# DSO_Control.net
KiCad netlist of a schematic drawn in Altium Designer
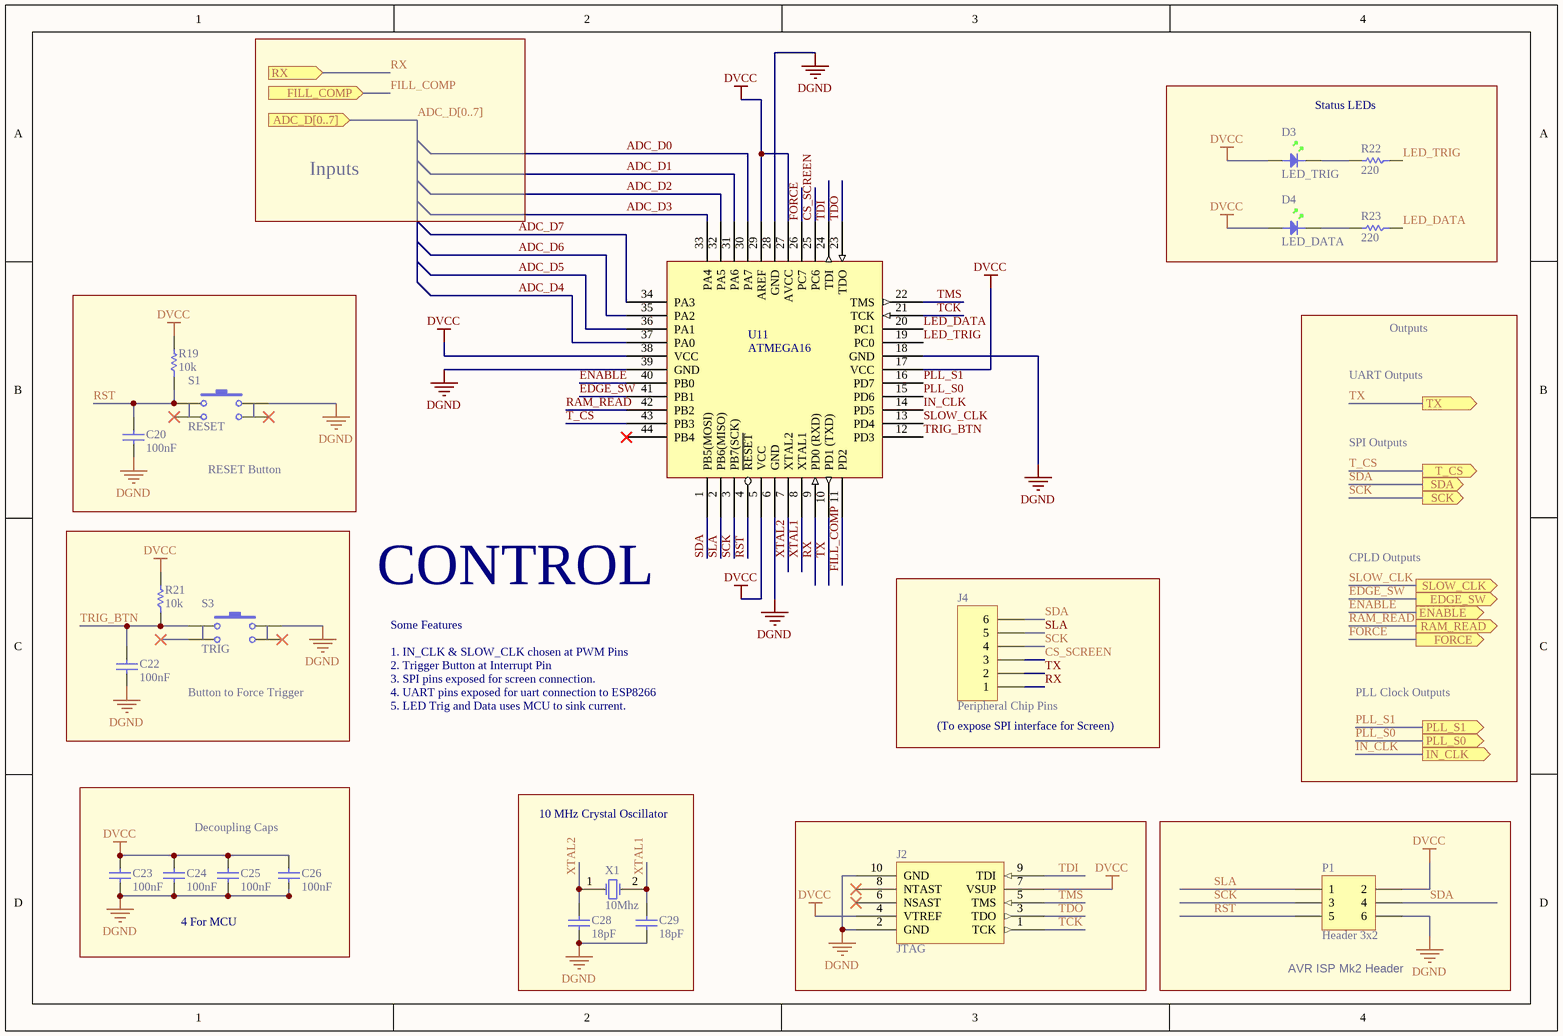
[diagram p0: DSO_Control.SchDoc]

(export (version "E")
  (design (tool "Eeschema 10.0.6"))
  (components
    (comp (ref "C20")
      (value "100nF")
      (footprint "0805C")
      (description "Capacitor")
      (fields (field (name "REVIEWED BY") "RM - 2018/08/05"))
      (libsource (lib "DSO") (part "C"))
    )
    (comp (ref "C22")
      (value "100nF")
      (footprint "0805C")
      (description "Capacitor")
      (fields (field (name "REVIEWED BY") "RM - 2018/08/05"))
      (libsource (lib "DSO") (part "C"))
    )
    (comp (ref "C23")
      (value "100nF")
      (footprint "0805C")
      (description "Capacitor")
      (fields (field (name "REVIEWED BY") "RM - 2018/08/05"))
      (libsource (lib "DSO") (part "C"))
    )
    (comp (ref "C24")
      (value "100nF")
      (footprint "0805C")
      (description "Capacitor")
      (fields (field (name "REVIEWED BY") "RM - 2018/08/05"))
      (libsource (lib "DSO") (part "C"))
    )
    (comp (ref "C25")
      (value "100nF")
      (footprint "0805C")
      (description "Capacitor")
      (fields (field (name "REVIEWED BY") "RM - 2018/08/05"))
      (libsource (lib "DSO") (part "C"))
    )
    (comp (ref "C26")
      (value "100nF")
      (footprint "0805C")
      (description "Capacitor")
      (fields (field (name "REVIEWED BY") "RM - 2018/08/05"))
      (libsource (lib "DSO") (part "C"))
    )
    (comp (ref "C28")
      (value "18pF")
      (footprint "0805C")
      (description "Capacitor")
      (fields (field (name "REVIEWED BY") "RM - 2018/08/05"))
      (libsource (lib "DSO") (part "C"))
    )
    (comp (ref "C29")
      (value "18pF")
      (footprint "0805C")
      (description "Capacitor")
      (fields (field (name "REVIEWED BY") "RM - 2018/08/05"))
      (libsource (lib "DSO") (part "C"))
    )
    (comp (ref "D3")
      (value "LED_TRIG")
      (footprint "0805D-GREEN")
      (description "Light Emitting Diode")
      (fields (field (name "REVIEWED BY") "RM - 2018/08/05"))
      (libsource (lib "DSO") (part "LED GREEN"))
    )
    (comp (ref "D4")
      (value "LED_DATA")
      (footprint "0805D-GREEN")
      (description "Light Emitting Diode")
      (fields (field (name "REVIEWED BY") "RM - 2018/08/05"))
      (libsource (lib "DSO") (part "LED GREEN"))
    )
    (comp (ref "J2")
      (value "JTAG")
      (footprint "BOXEDVERT10")
      (description "JTAG_CON")
      (fields (field (name "REVIEWED BY") "RM - 2018/08/05"))
      (libsource (lib "DSO") (part "JTAG_CON"))
    )
    (comp (ref "J4")
      (value "Peripheral Chip Pins")
      (footprint "HDR1X6")
      (description "Header, 6-Pin")
      (libsource (lib "DSO") (part "Header 6"))
    )
    (comp (ref "P1")
      (value "Header 3x2")
      (footprint "HDR3x2")
      (description "Header, 5-Pin")
      (fields (field (name "REVIEWED BY") "RM - 2018/08/05"))
      (libsource (lib "DSO") (part "Header 3x2"))
    )
    (comp (ref "R19")
      (value "10k")
      (footprint "0805")
      (description "Resistor")
      (fields (field (name "REVIEWED BY") "RM - 2018/08/05"))
      (libsource (lib "DSO") (part "R"))
    )
    (comp (ref "R21")
      (value "10k")
      (footprint "0805")
      (description "Resistor")
      (fields (field (name "REVIEWED BY") "RM - 2018/08/05"))
      (libsource (lib "DSO") (part "R"))
    )
    (comp (ref "R22")
      (value "220")
      (footprint "0805")
      (description "Resistor")
      (fields (field (name "REVIEWED BY") "RM - 2018/08/05"))
      (libsource (lib "DSO") (part "R"))
    )
    (comp (ref "R23")
      (value "220")
      (footprint "0805")
      (description "Resistor")
      (fields (field (name "REVIEWED BY") "RM - 2018/08/05"))
      (libsource (lib "DSO") (part "R"))
    )
    (comp (ref "S1")
      (value "RESET")
      (footprint "SPST PB SWITCH SMD")
      (description "Momentary Push Button Switch 1P 1T 2pins")
      (fields (field (name "REVIEWED BY") "RM - 2018/08/05"))
      (libsource (lib "DSO") (part "SW_PB_1P1T4"))
    )
    (comp (ref "S3")
      (value "TRIG")
      (footprint "SPST PB SWITCH SMD")
      (description "Momentary Push Button Switch 1P 1T 2pins")
      (fields (field (name "REVIEWED BY") "RM - 2018/08/05"))
      (libsource (lib "DSO") (part "SW_PB_1P1T4"))
    )
    (comp (ref "U11")
      (value "ATMEGA16")
      (footprint "QFP-48")
      (description "ATMEGA16 Microcontroller")
      (fields (field (name "REVIEWED BY") "RM - 2018/08/05"))
      (libsource (lib "DSO") (part "ATMEGA16"))
    )
    (comp (ref "X1")
      (value "10Mhz")
      (footprint "XTAL_FLAT_SMD")
      (description "Crystal Oscillator")
      (fields (field (name "REVIEWED BY") "RM - 2018/08/05"))
      (libsource (lib "DSO") (part "XTAL"))
    )
  )
  (nets
    (net (code "1") (name "/ADC_D0") (class "Default")
      (node (ref "U11") (pin "30") (pinfunction "PA7_30") (pintype "passive"))
    )
    (net (code "2") (name "/ADC_D1") (class "Default")
      (node (ref "U11") (pin "31") (pinfunction "PA6_31") (pintype "passive"))
    )
    (net (code "3") (name "/ADC_D2") (class "Default")
      (node (ref "U11") (pin "32") (pinfunction "PA5_32") (pintype "passive"))
    )
    (net (code "4") (name "/ADC_D3") (class "Default")
      (node (ref "U11") (pin "33") (pinfunction "PA4_33") (pintype "passive"))
    )
    (net (code "5") (name "/ADC_D4") (class "Default")
      (node (ref "U11") (pin "37") (pinfunction "PA0_37") (pintype "passive"))
    )
    (net (code "6") (name "/ADC_D5") (class "Default")
      (node (ref "U11") (pin "36") (pinfunction "PA1_36") (pintype "passive"))
    )
    (net (code "7") (name "/ADC_D6") (class "Default")
      (node (ref "U11") (pin "35") (pinfunction "PA2_35") (pintype "passive"))
    )
    (net (code "8") (name "/ADC_D7") (class "Default")
      (node (ref "U11") (pin "34") (pinfunction "PA3_34") (pintype "passive"))
    )
    (net (code "10") (name "/CS_SCREEN") (class "Default")
      (node (ref "J4") (pin "3") (pinfunction "3_3") (pintype "passive"))
      (node (ref "U11") (pin "25") (pinfunction "PC6_25") (pintype "passive"))
    )
    (net (code "11") (name "/EDGE_SW") (class "Default")
      (node (ref "U11") (pin "41") (pinfunction "PB1_41") (pintype "passive"))
    )
    (net (code "12") (name "/ENABLE") (class "Default")
      (node (ref "U11") (pin "40") (pinfunction "PB0_40") (pintype "passive"))
    )
    (net (code "13") (name "/FILL_COMP") (class "Default")
      (node (ref "U11") (pin "11") (pinfunction "PD2_11") (pintype "passive"))
    )
    (net (code "14") (name "/FORCE") (class "Default")
      (node (ref "U11") (pin "26") (pinfunction "PC7_26") (pintype "passive"))
    )
    (net (code "15") (name "/IN_CLK") (class "Default")
      (node (ref "U11") (pin "14") (pinfunction "PD5_14") (pintype "passive"))
    )
    (net (code "16") (name "/LED_DATA") (class "Default")
      (node (ref "R23") (pin "1") (pintype "passive"))
      (node (ref "U11") (pin "20") (pinfunction "PC1_20") (pintype "passive"))
    )
    (net (code "17") (name "/LED_TRIG") (class "Default")
      (node (ref "R22") (pin "1") (pintype "passive"))
      (node (ref "U11") (pin "19") (pinfunction "PC0_19") (pintype "passive"))
    )
    (net (code "18") (name "/PLL_S0") (class "Default")
      (node (ref "U11") (pin "15") (pinfunction "PD6_15") (pintype "passive"))
    )
    (net (code "19") (name "/PLL_S1") (class "Default")
      (node (ref "U11") (pin "16") (pinfunction "PD7_16") (pintype "passive"))
    )
    (net (code "20") (name "/RAM_READ") (class "Default")
      (node (ref "U11") (pin "42") (pinfunction "PB2_42") (pintype "passive"))
    )
    (net (code "21") (name "/RST") (class "Default")
      (node (ref "C20") (pin "1") (pinfunction "1_1") (pintype "passive"))
      (node (ref "P1") (pin "5") (pinfunction "5_5") (pintype "passive"))
      (node (ref "R19") (pin "1") (pintype "passive"))
      (node (ref "S1") (pin "1") (pinfunction "1_1") (pintype "passive"))
      (node (ref "U11") (pin "4") (pinfunction "~{RESET}_4") (pintype "passive"))
    )
    (net (code "22") (name "/RX") (class "Default")
      (node (ref "J4") (pin "1") (pinfunction "1_1") (pintype "passive"))
      (node (ref "U11") (pin "9") (pinfunction "PD0_(RXD)_9") (pintype "input"))
    )
    (net (code "23") (name "/SCK") (class "Default")
      (node (ref "J4") (pin "4") (pinfunction "4_4") (pintype "passive"))
      (node (ref "P1") (pin "3") (pinfunction "3_3") (pintype "passive"))
      (node (ref "U11") (pin "3") (pinfunction "PB7(SCK)_3") (pintype "passive"))
    )
    (net (code "24") (name "/SDA") (class "Default")
      (node (ref "J4") (pin "6") (pinfunction "6_6") (pintype "passive"))
      (node (ref "P1") (pin "4") (pinfunction "4_4") (pintype "passive"))
      (node (ref "U11") (pin "1") (pinfunction "PB5(MOSI)_1") (pintype "passive"))
    )
    (net (code "25") (name "/SLA") (class "Default")
      (node (ref "J4") (pin "5") (pinfunction "5_5") (pintype "passive"))
      (node (ref "P1") (pin "1") (pinfunction "1_1") (pintype "passive"))
      (node (ref "U11") (pin "2") (pinfunction "PB6(MISO)_2") (pintype "passive"))
    )
    (net (code "26") (name "/SLOW_CLK") (class "Default")
      (node (ref "U11") (pin "13") (pinfunction "PD4_13") (pintype "passive"))
    )
    (net (code "27") (name "/TCK") (class "Default")
      (node (ref "J2") (pin "1") (pinfunction "TCK_1") (pintype "output"))
      (node (ref "U11") (pin "21") (pinfunction "TCK_21") (pintype "input"))
    )
    (net (code "28") (name "/TDI") (class "Default")
      (node (ref "J2") (pin "9") (pinfunction "TDI_9") (pintype "input"))
      (node (ref "U11") (pin "24") (pinfunction "TDI_24") (pintype "output"))
    )
    (net (code "29") (name "/TDO") (class "Default")
      (node (ref "J2") (pin "3") (pinfunction "TDO_3") (pintype "output"))
      (node (ref "U11") (pin "23") (pinfunction "TDO_23") (pintype "input"))
    )
    (net (code "30") (name "/TMS") (class "Default")
      (node (ref "J2") (pin "5") (pinfunction "TMS_5") (pintype "input"))
      (node (ref "U11") (pin "22") (pinfunction "TMS_22") (pintype "output"))
    )
    (net (code "31") (name "/TRIG_BTN") (class "Default")
      (node (ref "C22") (pin "1") (pinfunction "1_1") (pintype "passive"))
      (node (ref "R21") (pin "1") (pintype "passive"))
      (node (ref "S3") (pin "1") (pinfunction "1_1") (pintype "passive"))
      (node (ref "U11") (pin "12") (pinfunction "PD3_12") (pintype "passive"))
    )
    (net (code "32") (name "/TX") (class "Default")
      (node (ref "J4") (pin "2") (pinfunction "2_2") (pintype "passive"))
      (node (ref "U11") (pin "10") (pinfunction "PD1_(TXD)_10") (pintype "output"))
    )
    (net (code "33") (name "/T_CS") (class "Default")
      (node (ref "U11") (pin "43") (pinfunction "PB3_43") (pintype "passive"))
    )
    (net (code "34") (name "/XTAL1") (class "Default")
      (node (ref "C29") (pin "1") (pinfunction "1_1") (pintype "passive"))
      (node (ref "U11") (pin "8") (pinfunction "XTAL1_8") (pintype "passive"))
      (node (ref "X1") (pin "2") (pinfunction "OSC2_2") (pintype "passive"))
    )
    (net (code "35") (name "/XTAL2") (class "Default")
      (node (ref "C28") (pin "1") (pinfunction "1_1") (pintype "passive"))
      (node (ref "U11") (pin "7") (pinfunction "XTAL2_7") (pintype "passive"))
      (node (ref "X1") (pin "1") (pinfunction "OSC1_1") (pintype "passive"))
    )
    (net (code "36") (name "DGND") (class "Default")
      (node (ref "C20") (pin "2") (pinfunction "2_2") (pintype "passive"))
      (node (ref "C22") (pin "2") (pinfunction "2_2") (pintype "passive"))
      (node (ref "C23") (pin "2") (pinfunction "2_2") (pintype "passive"))
      (node (ref "C24") (pin "2") (pinfunction "2_2") (pintype "passive"))
      (node (ref "C25") (pin "2") (pinfunction "2_2") (pintype "passive"))
      (node (ref "C26") (pin "2") (pinfunction "2_2") (pintype "passive"))
      (node (ref "C28") (pin "2") (pinfunction "2_2") (pintype "passive"))
      (node (ref "C29") (pin "2") (pinfunction "2_2") (pintype "passive"))
      (node (ref "J2") (pin "10") (pinfunction "GND_10") (pintype "passive"))
      (node (ref "J2") (pin "2") (pinfunction "GND_2") (pintype "passive"))
      (node (ref "P1") (pin "6") (pinfunction "6_6") (pintype "passive"))
      (node (ref "S1") (pin "2") (pinfunction "2_2") (pintype "passive"))
      (node (ref "S3") (pin "2") (pinfunction "2_2") (pintype "passive"))
      (node (ref "U11") (pin "18") (pinfunction "GND_18") (pintype "passive"))
      (node (ref "U11") (pin "28") (pinfunction "GND_28") (pintype "passive"))
      (node (ref "U11") (pin "39") (pinfunction "GND_39") (pintype "passive"))
      (node (ref "U11") (pin "6") (pinfunction "GND_6") (pintype "passive"))
    )
    (net (code "37") (name "DVCC") (class "Default")
      (node (ref "C23") (pin "1") (pinfunction "1_1") (pintype "passive"))
      (node (ref "C24") (pin "1") (pinfunction "1_1") (pintype "passive"))
      (node (ref "C25") (pin "1") (pinfunction "1_1") (pintype "passive"))
      (node (ref "C26") (pin "1") (pinfunction "1_1") (pintype "passive"))
      (node (ref "D3") (pin "A") (pinfunction "A_A") (pintype "passive"))
      (node (ref "D4") (pin "A") (pinfunction "A_A") (pintype "passive"))
      (node (ref "J2") (pin "4") (pinfunction "VTREF_4") (pintype "power_in"))
      (node (ref "J2") (pin "7") (pinfunction "VSUP_7") (pintype "passive"))
      (node (ref "P1") (pin "2") (pinfunction "2_2") (pintype "passive"))
      (node (ref "R19") (pin "2") (pintype "passive"))
      (node (ref "R21") (pin "2") (pintype "passive"))
      (node (ref "U11") (pin "17") (pinfunction "VCC_17") (pintype "passive"))
      (node (ref "U11") (pin "27") (pinfunction "AVCC_27") (pintype "passive"))
      (node (ref "U11") (pin "29") (pinfunction "AREF_29") (pintype "passive"))
      (node (ref "U11") (pin "38") (pinfunction "VCC_38") (pintype "passive"))
      (node (ref "U11") (pin "5") (pinfunction "VCC_5") (pintype "passive"))
    )
    (net (code "38") (name "Net-(D3-PadK)") (class "Default")
      (node (ref "D3") (pin "K") (pinfunction "K_K") (pintype "passive"))
      (node (ref "R22") (pin "2") (pintype "passive"))
    )
    (net (code "39") (name "Net-(D4-PadK)") (class "Default")
      (node (ref "D4") (pin "K") (pinfunction "K_K") (pintype "passive"))
      (node (ref "R23") (pin "2") (pintype "passive"))
    )
    (net (code "40") (name "unconnected-(J2-NSAST-Pad6)") (class "Default")
      (node (ref "J2") (pin "6") (pinfunction "NSAST_6") (pintype "passive+no_connect"))
    )
    (net (code "41") (name "unconnected-(J2-NTAST-Pad8)") (class "Default")
      (node (ref "J2") (pin "8") (pinfunction "NTAST_8") (pintype "passive+no_connect"))
    )
    (net (code "42") (name "unconnected-(S1-Pad3)") (class "Default")
      (node (ref "S1") (pin "3") (pinfunction "3_3") (pintype "passive+no_connect"))
    )
    (net (code "43") (name "unconnected-(S1-Pad4)") (class "Default")
      (node (ref "S1") (pin "4") (pinfunction "4_4") (pintype "passive+no_connect"))
    )
    (net (code "44") (name "unconnected-(S3-Pad3)") (class "Default")
      (node (ref "S3") (pin "3") (pinfunction "3_3") (pintype "passive+no_connect"))
    )
    (net (code "45") (name "unconnected-(S3-Pad4)") (class "Default")
      (node (ref "S3") (pin "4") (pinfunction "4_4") (pintype "passive+no_connect"))
    )
    (net (code "46") (name "unconnected-(U11-PB4-Pad44)") (class "Default")
      (node (ref "U11") (pin "44") (pinfunction "PB4_44") (pintype "passive+no_connect"))
    )
  )
)
